# nonregulation-level-shifter-mk-1_0.net
KiCad netlist of a schematic drawn in EAGLE
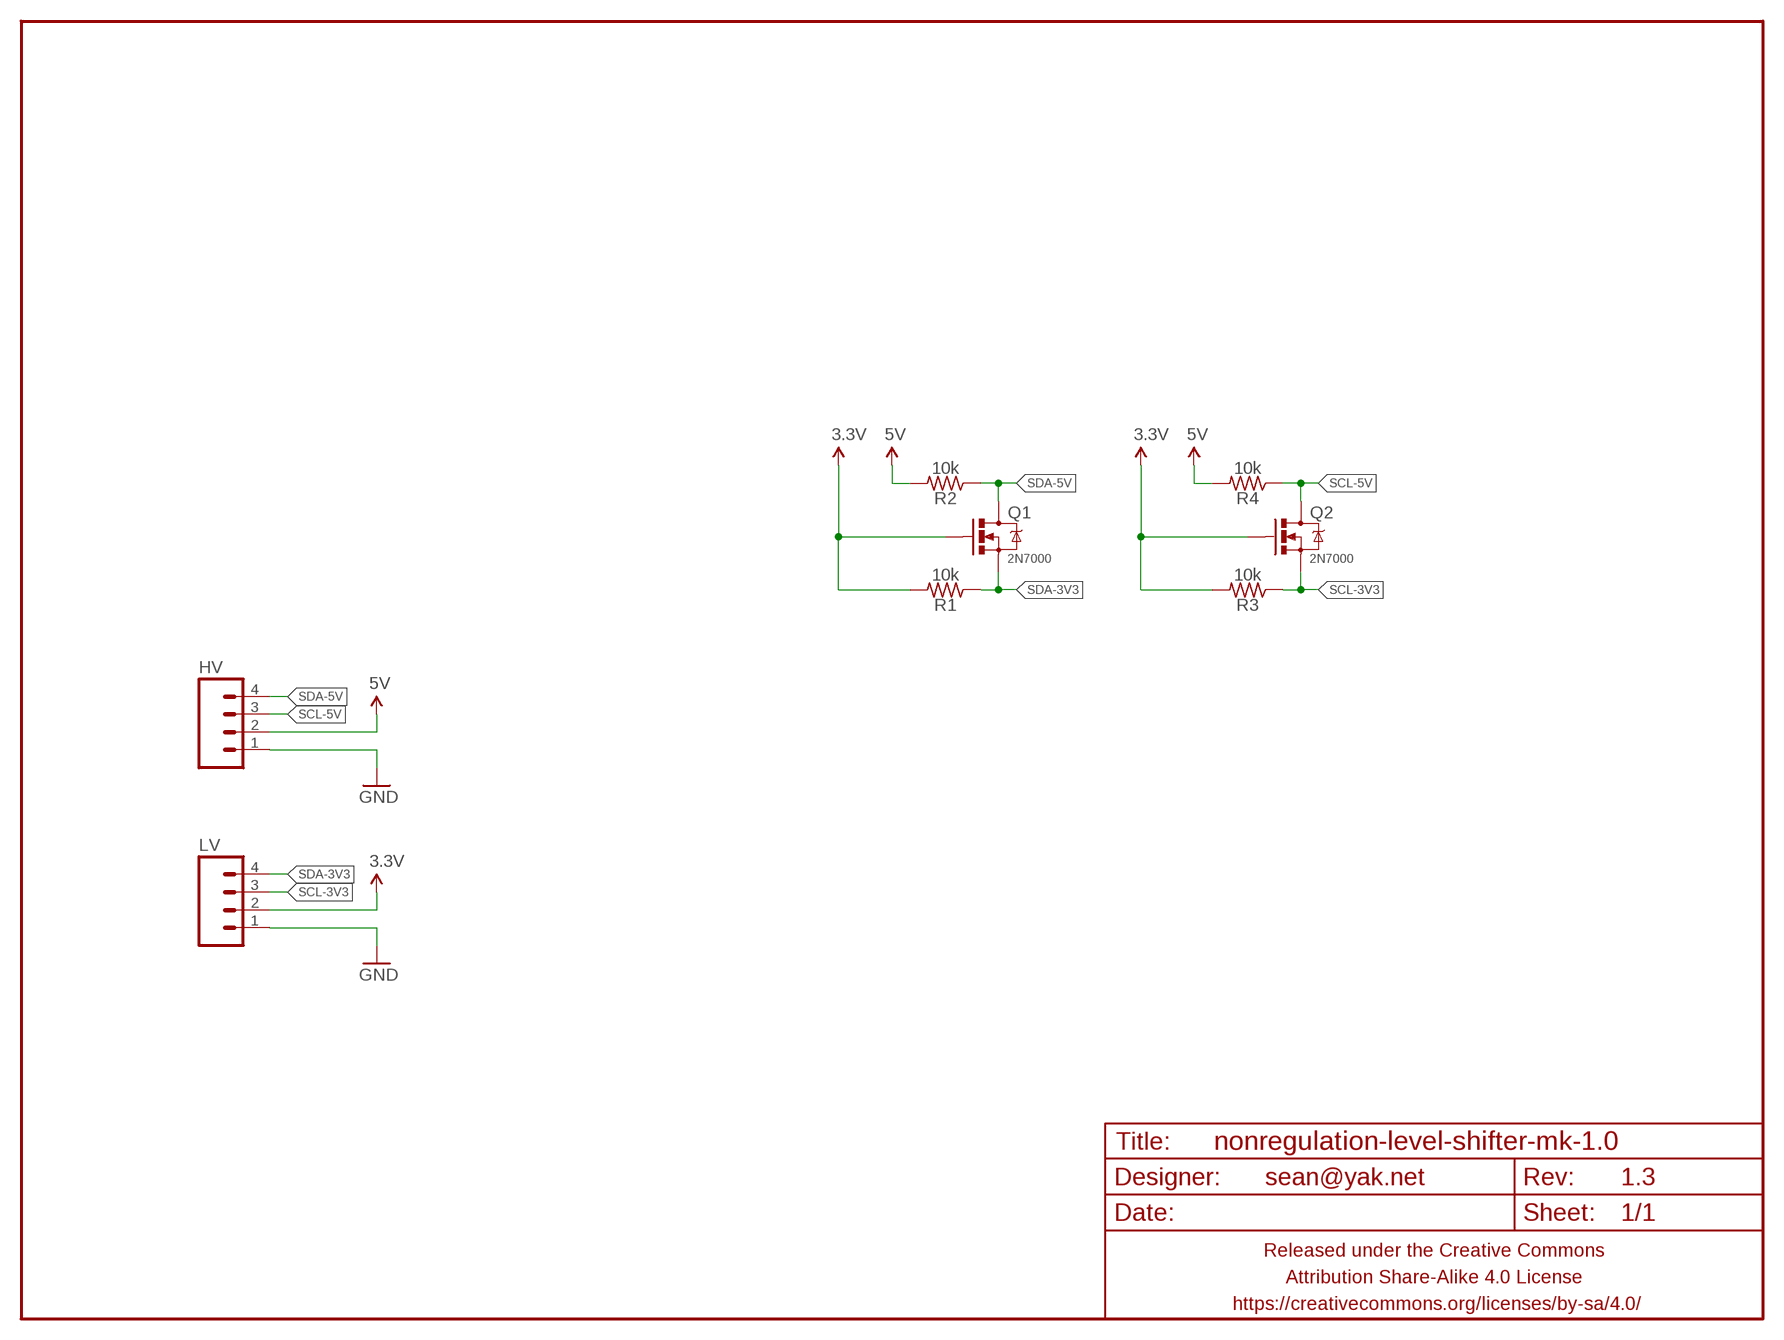
[diagram p0: schematic, sheet 1]

(export (version "E")
  (design (tool "Eeschema 10.0.6"))
  (components
    (comp (ref "FRAME1")
      (value "FRAME-LETTERNO_PACKAGE")
      (footprint "eagle-import:DUMMY")
      (fields (field (name "DESIGNER") "sean@yak.net") (field (name "VERSION") "1.3"))
      (libsource (lib "eagle-import") (part "FRAME-LETTERNO_PACKAGE"))
    )
    (comp (ref "HV")
      (value "M04PTH")
      (footprint "eagle-import:1X04-PTH-VERT")
      (libsource (lib "eagle-import") (part "M04PTH"))
    )
    (comp (ref "LV")
      (value "M04PTH")
      (footprint "eagle-import:1X04-PTH-VERT")
      (libsource (lib "eagle-import") (part "M04PTH"))
    )
    (comp (ref "Q1")
      (value "2N7000")
      (footprint "eagle-import:TO-92-AMMO")
      (libsource (lib "eagle-import") (part "MOSFET-NCHANNEL2N7000-AMMO"))
    )
    (comp (ref "Q2")
      (value "2N7000")
      (footprint "eagle-import:TO-92-AMMO")
      (libsource (lib "eagle-import") (part "MOSFET-NCHANNEL2N7000-AMMO"))
    )
    (comp (ref "R1")
      (value "10k")
      (footprint "eagle-import:RESISTOR-AXIAL-PTH-5.08MM")
      (libsource (lib "eagle-import") (part "RESISTORPTH-AXIAL-5.08MM"))
    )
    (comp (ref "R2")
      (value "10k")
      (footprint "eagle-import:RESISTOR-AXIAL-PTH-5.08MM")
      (libsource (lib "eagle-import") (part "RESISTORPTH-AXIAL-5.08MM"))
    )
    (comp (ref "R3")
      (value "10k")
      (footprint "eagle-import:RESISTOR-AXIAL-PTH-5.08MM")
      (libsource (lib "eagle-import") (part "RESISTORPTH-AXIAL-5.08MM"))
    )
    (comp (ref "R4")
      (value "10k")
      (footprint "eagle-import:RESISTOR-AXIAL-PTH-5.08MM")
      (libsource (lib "eagle-import") (part "RESISTORPTH-AXIAL-5.08MM"))
    )
  )
  (nets
    (net (code "1") (name "3.3V") (class "Default")
      (node (ref "LV") (pin "2") (pinfunction "2_2") (pintype "passive"))
      (node (ref "Q1") (pin "2") (pinfunction "G_2") (pintype "passive"))
      (node (ref "Q2") (pin "2") (pinfunction "G_2") (pintype "passive"))
      (node (ref "R1") (pin "P$2") (pinfunction "2_P$2") (pintype "passive"))
      (node (ref "R3") (pin "P$2") (pinfunction "2_P$2") (pintype "passive"))
    )
    (net (code "2") (name "5V") (class "Default")
      (node (ref "HV") (pin "2") (pinfunction "2_2") (pintype "passive"))
      (node (ref "R2") (pin "P$2") (pinfunction "2_P$2") (pintype "passive"))
      (node (ref "R4") (pin "P$2") (pinfunction "2_P$2") (pintype "passive"))
    )
    (net (code "3") (name "GND") (class "Default")
      (node (ref "HV") (pin "1") (pinfunction "1_1") (pintype "passive"))
      (node (ref "LV") (pin "1") (pinfunction "1_1") (pintype "passive"))
    )
    (net (code "4") (name "SCL-3V3") (class "Default")
      (node (ref "LV") (pin "3") (pinfunction "3_3") (pintype "passive"))
      (node (ref "Q2") (pin "1") (pinfunction "S_1") (pintype "passive"))
      (node (ref "R3") (pin "P$1") (pinfunction "1_P$1") (pintype "passive"))
    )
    (net (code "5") (name "SCL-5V") (class "Default")
      (node (ref "HV") (pin "3") (pinfunction "3_3") (pintype "passive"))
      (node (ref "Q2") (pin "3") (pinfunction "D_3") (pintype "passive"))
      (node (ref "R4") (pin "P$1") (pinfunction "1_P$1") (pintype "passive"))
    )
    (net (code "6") (name "SDA-3V3") (class "Default")
      (node (ref "LV") (pin "4") (pinfunction "4_4") (pintype "passive"))
      (node (ref "Q1") (pin "1") (pinfunction "S_1") (pintype "passive"))
      (node (ref "R1") (pin "P$1") (pinfunction "1_P$1") (pintype "passive"))
    )
    (net (code "7") (name "SDA-5V") (class "Default")
      (node (ref "HV") (pin "4") (pinfunction "4_4") (pintype "passive"))
      (node (ref "Q1") (pin "3") (pinfunction "D_3") (pintype "passive"))
      (node (ref "R2") (pin "P$1") (pinfunction "1_P$1") (pintype "passive"))
    )
  )
)
